# LED.net
KiCad netlist of a schematic drawn in Altium Designer
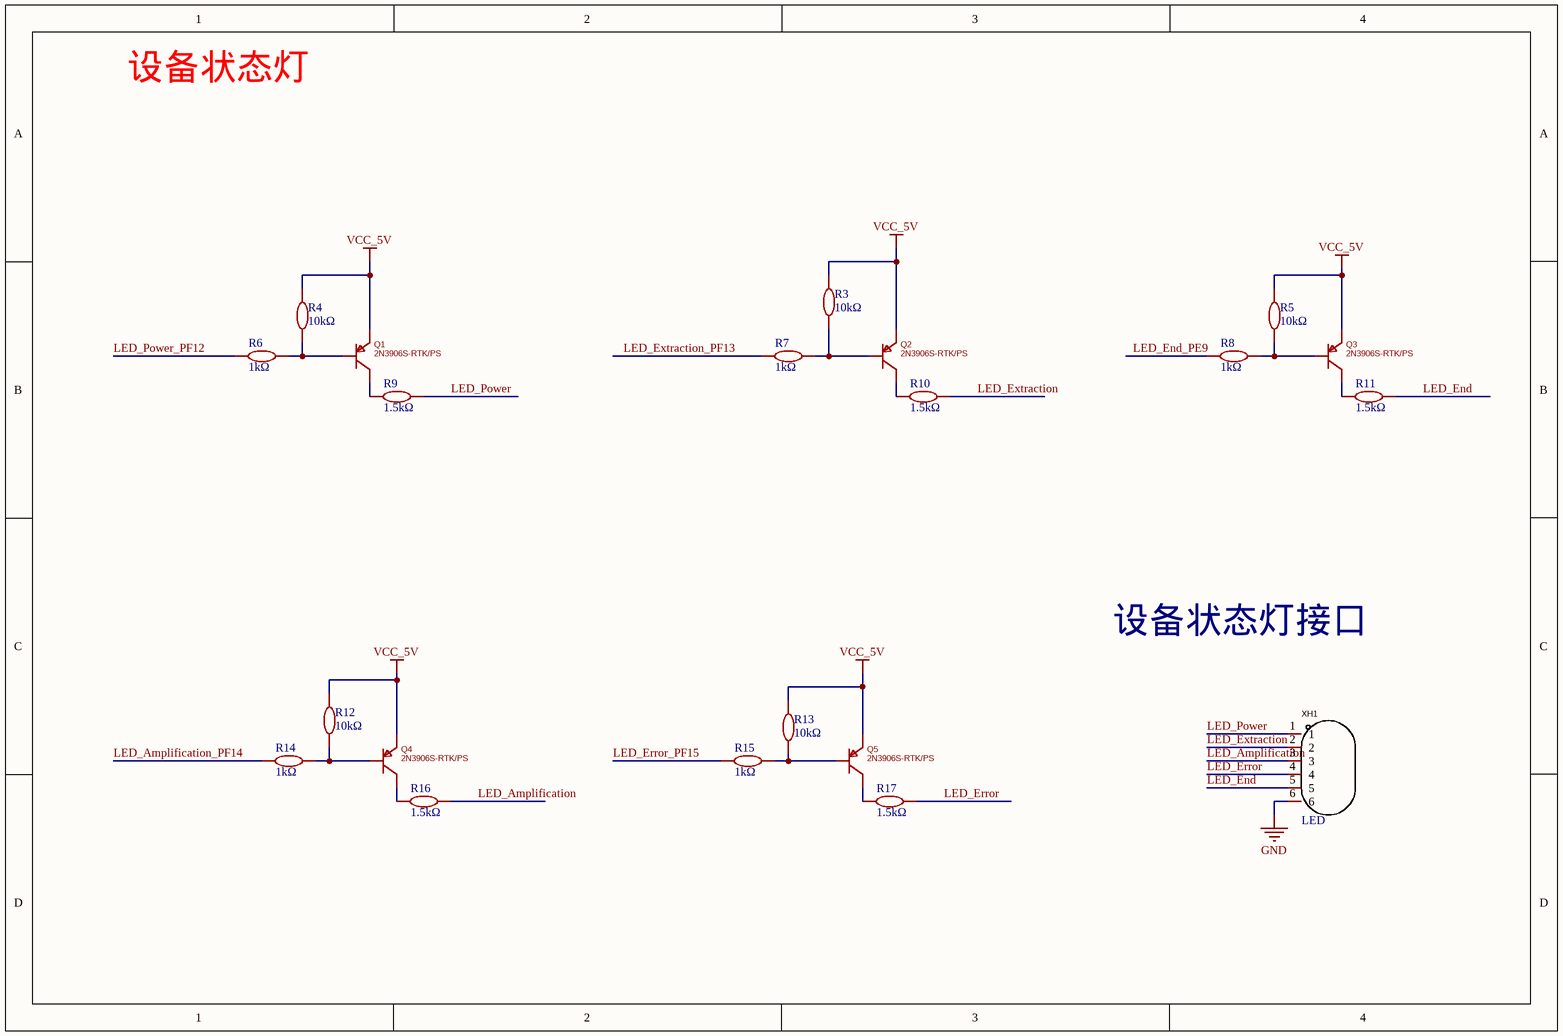
[diagram p0: LED.SchDoc]

(export (version "E")
  (design (tool "Eeschema 10.0.6"))
  (components
    (comp (ref "Q1")
      (value "2N3906S-RTK/PS")
      (footprint "SOT-23-3_L2.9-W1.3-P1.90-LS2.4-TR")
      (fields (field (name "MANUFACTURER") "KEC"))
      (libsource (lib "XG_DW_POCT_2K10LED_3") (part "2N3906S-RTK/PS"))
    )
    (comp (ref "Q2")
      (value "2N3906S-RTK/PS")
      (footprint "SOT-23-3_L2.9-W1.3-P1.90-LS2.4-TR")
      (fields (field (name "MANUFACTURER") "KEC"))
      (libsource (lib "XG_DW_POCT_2K10LED_3") (part "2N3906S-RTK/PS"))
    )
    (comp (ref "Q3")
      (value "2N3906S-RTK/PS")
      (footprint "SOT-23-3_L2.9-W1.3-P1.90-LS2.4-TR")
      (fields (field (name "MANUFACTURER") "KEC"))
      (libsource (lib "XG_DW_POCT_2K10LED_3") (part "2N3906S-RTK/PS"))
    )
    (comp (ref "Q4")
      (value "2N3906S-RTK/PS")
      (footprint "SOT-23-3_L2.9-W1.3-P1.90-LS2.4-TR")
      (fields (field (name "MANUFACTURER") "KEC"))
      (libsource (lib "XG_DW_POCT_2K10LED_3") (part "2N3906S-RTK/PS"))
    )
    (comp (ref "Q5")
      (value "2N3906S-RTK/PS")
      (footprint "SOT-23-3_L2.9-W1.3-P1.90-LS2.4-TR")
      (fields (field (name "MANUFACTURER") "KEC"))
      (libsource (lib "XG_DW_POCT_2K10LED_3") (part "2N3906S-RTK/PS"))
    )
    (comp (ref "R3")
      (value "10kΩ")
      (footprint "R0603")
      (description "电阻类型:厚膜电阻;阻值:10kΩ;精度:±1%;功率:100mW;最大工作电压:75V;温度系数:±100ppm/℃;")
      (libsource (lib "XG_DW_POCT_2K10LED_3") (part "10kΩ,R0603"))
    )
    (comp (ref "R4")
      (value "10kΩ")
      (footprint "R0603")
      (description "电阻类型:厚膜电阻;阻值:10kΩ;精度:±1%;功率:100mW;最大工作电压:75V;温度系数:±100ppm/℃;")
      (libsource (lib "XG_DW_POCT_2K10LED_3") (part "10kΩ,R0603"))
    )
    (comp (ref "R5")
      (value "10kΩ")
      (footprint "R0603")
      (description "电阻类型:厚膜电阻;阻值:10kΩ;精度:±1%;功率:100mW;最大工作电压:75V;温度系数:±100ppm/℃;")
      (libsource (lib "XG_DW_POCT_2K10LED_3") (part "10kΩ,R0603"))
    )
    (comp (ref "R6")
      (value "1kΩ")
      (footprint "R0603")
      (description "电阻类型:厚膜电阻;阻值:1kΩ;精度:±1%;功率:125mW;最大工作电压:150V;温度系数:±100ppm/℃;")
      (libsource (lib "XG_DW_POCT_2K10LED_3") (part "1kΩ,R0603"))
    )
    (comp (ref "R7")
      (value "1kΩ")
      (footprint "R0603")
      (description "电阻类型:厚膜电阻;阻值:1kΩ;精度:±1%;功率:125mW;最大工作电压:150V;温度系数:±100ppm/℃;")
      (libsource (lib "XG_DW_POCT_2K10LED_3") (part "1kΩ,R0603"))
    )
    (comp (ref "R8")
      (value "1kΩ")
      (footprint "R0603")
      (description "电阻类型:厚膜电阻;阻值:1kΩ;精度:±1%;功率:125mW;最大工作电压:150V;温度系数:±100ppm/℃;")
      (libsource (lib "XG_DW_POCT_2K10LED_3") (part "1kΩ,R0603"))
    )
    (comp (ref "R9")
      (value "1.5kΩ")
      (footprint "R0603")
      (description "电阻类型:厚膜电阻;阻值:1.5kΩ;精度:±1%;功率:100mW;最大工作电压:75V;温度系数:±100ppm/℃;")
      (libsource (lib "XG_DW_POCT_2K10LED_3") (part "1.5kΩ,R0603"))
    )
    (comp (ref "R10")
      (value "1.5kΩ")
      (footprint "R0603")
      (description "电阻类型:厚膜电阻;阻值:1.5kΩ;精度:±1%;功率:100mW;最大工作电压:75V;温度系数:±100ppm/℃;")
      (libsource (lib "XG_DW_POCT_2K10LED_3") (part "1.5kΩ,R0603"))
    )
    (comp (ref "R11")
      (value "1.5kΩ")
      (footprint "R0603")
      (description "电阻类型:厚膜电阻;阻值:1.5kΩ;精度:±1%;功率:100mW;最大工作电压:75V;温度系数:±100ppm/℃;")
      (libsource (lib "XG_DW_POCT_2K10LED_3") (part "1.5kΩ,R0603"))
    )
    (comp (ref "R12")
      (value "10kΩ")
      (footprint "R0603")
      (description "电阻类型:厚膜电阻;阻值:10kΩ;精度:±1%;功率:100mW;最大工作电压:75V;温度系数:±100ppm/℃;")
      (libsource (lib "XG_DW_POCT_2K10LED_3") (part "10kΩ,R0603"))
    )
    (comp (ref "R13")
      (value "10kΩ")
      (footprint "R0603")
      (description "电阻类型:厚膜电阻;阻值:10kΩ;精度:±1%;功率:100mW;最大工作电压:75V;温度系数:±100ppm/℃;")
      (libsource (lib "XG_DW_POCT_2K10LED_3") (part "10kΩ,R0603"))
    )
    (comp (ref "R14")
      (value "1kΩ")
      (footprint "R0603")
      (description "电阻类型:厚膜电阻;阻值:1kΩ;精度:±1%;功率:125mW;最大工作电压:150V;温度系数:±100ppm/℃;")
      (libsource (lib "XG_DW_POCT_2K10LED_3") (part "1kΩ,R0603"))
    )
    (comp (ref "R15")
      (value "1kΩ")
      (footprint "R0603")
      (description "电阻类型:厚膜电阻;阻值:1kΩ;精度:±1%;功率:125mW;最大工作电压:150V;温度系数:±100ppm/℃;")
      (libsource (lib "XG_DW_POCT_2K10LED_3") (part "1kΩ,R0603"))
    )
    (comp (ref "R16")
      (value "1.5kΩ")
      (footprint "R0603")
      (description "电阻类型:厚膜电阻;阻值:1.5kΩ;精度:±1%;功率:100mW;最大工作电压:75V;温度系数:±100ppm/℃;")
      (libsource (lib "XG_DW_POCT_2K10LED_3") (part "1.5kΩ,R0603"))
    )
    (comp (ref "R17")
      (value "1.5kΩ")
      (footprint "R0603")
      (description "电阻类型:厚膜电阻;阻值:1.5kΩ;精度:±1%;功率:100mW;最大工作电压:75V;温度系数:±100ppm/℃;")
      (libsource (lib "XG_DW_POCT_2K10LED_3") (part "1.5kΩ,R0603"))
    )
    (comp (ref "XH1")
      (value "LED")
      (footprint "CONN-TH_6P-P2.00_S6B-PH-K-S-LF-SN")
      (libsource (lib "XG_DW_POCT_2K10LED_3") (part "S6B-PH-K-S(LF)(SN)"))
    )
  )
  (nets
    (net (code "1") (name "/LED_Amplification") (class "Default")
      (node (ref "R16") (pin "1") (pinfunction "1_1") (pintype "passive"))
      (node (ref "XH1") (pin "3") (pinfunction "3_3") (pintype "passive"))
    )
    (net (code "2") (name "/LED_Amplification_PF14") (class "Default")
      (node (ref "R14") (pin "2") (pinfunction "2_2") (pintype "passive"))
    )
    (net (code "3") (name "/LED_End") (class "Default")
      (node (ref "R11") (pin "1") (pinfunction "1_1") (pintype "passive"))
      (node (ref "XH1") (pin "5") (pinfunction "5_5") (pintype "passive"))
    )
    (net (code "4") (name "/LED_End_PE9") (class "Default")
      (node (ref "R8") (pin "2") (pinfunction "2_2") (pintype "passive"))
    )
    (net (code "5") (name "/LED_Error") (class "Default")
      (node (ref "R17") (pin "1") (pinfunction "1_1") (pintype "passive"))
      (node (ref "XH1") (pin "4") (pinfunction "4_4") (pintype "passive"))
    )
    (net (code "6") (name "/LED_Error_PF15") (class "Default")
      (node (ref "R15") (pin "2") (pinfunction "2_2") (pintype "passive"))
    )
    (net (code "7") (name "/LED_Extraction") (class "Default")
      (node (ref "R10") (pin "1") (pinfunction "1_1") (pintype "passive"))
      (node (ref "XH1") (pin "2") (pinfunction "2_2") (pintype "passive"))
    )
    (net (code "8") (name "/LED_Extraction_PF13") (class "Default")
      (node (ref "R7") (pin "2") (pinfunction "2_2") (pintype "passive"))
    )
    (net (code "9") (name "/LED_Power") (class "Default")
      (node (ref "R9") (pin "2") (pinfunction "2_2") (pintype "passive"))
      (node (ref "XH1") (pin "1") (pinfunction "1_1") (pintype "passive"))
    )
    (net (code "10") (name "/LED_Power_PF12") (class "Default")
      (node (ref "R6") (pin "2") (pinfunction "2_2") (pintype "passive"))
    )
    (net (code "11") (name "GND") (class "Default")
      (node (ref "XH1") (pin "6") (pinfunction "6_6") (pintype "passive"))
    )
    (net (code "12") (name "Net-(Q1-B)") (class "Default")
      (node (ref "Q1") (pin "2") (pinfunction "B_2") (pintype "passive"))
      (node (ref "R4") (pin "1") (pinfunction "1_1") (pintype "passive"))
      (node (ref "R6") (pin "1") (pinfunction "1_1") (pintype "passive"))
    )
    (net (code "13") (name "Net-(Q1-C)") (class "Default")
      (node (ref "Q1") (pin "3") (pinfunction "C_3") (pintype "passive"))
      (node (ref "R9") (pin "1") (pinfunction "1_1") (pintype "passive"))
    )
    (net (code "14") (name "Net-(Q2-B)") (class "Default")
      (node (ref "Q2") (pin "2") (pinfunction "B_2") (pintype "passive"))
      (node (ref "R3") (pin "1") (pinfunction "1_1") (pintype "passive"))
      (node (ref "R7") (pin "1") (pinfunction "1_1") (pintype "passive"))
    )
    (net (code "15") (name "Net-(Q2-C)") (class "Default")
      (node (ref "Q2") (pin "3") (pinfunction "C_3") (pintype "passive"))
      (node (ref "R10") (pin "2") (pinfunction "2_2") (pintype "passive"))
    )
    (net (code "16") (name "Net-(Q3-B)") (class "Default")
      (node (ref "Q3") (pin "2") (pinfunction "B_2") (pintype "passive"))
      (node (ref "R5") (pin "1") (pinfunction "1_1") (pintype "passive"))
      (node (ref "R8") (pin "1") (pinfunction "1_1") (pintype "passive"))
    )
    (net (code "17") (name "Net-(Q3-C)") (class "Default")
      (node (ref "Q3") (pin "3") (pinfunction "C_3") (pintype "passive"))
      (node (ref "R11") (pin "2") (pinfunction "2_2") (pintype "passive"))
    )
    (net (code "18") (name "Net-(Q4-B)") (class "Default")
      (node (ref "Q4") (pin "2") (pinfunction "B_2") (pintype "passive"))
      (node (ref "R12") (pin "1") (pinfunction "1_1") (pintype "passive"))
      (node (ref "R14") (pin "1") (pinfunction "1_1") (pintype "passive"))
    )
    (net (code "19") (name "Net-(Q4-C)") (class "Default")
      (node (ref "Q4") (pin "3") (pinfunction "C_3") (pintype "passive"))
      (node (ref "R16") (pin "2") (pinfunction "2_2") (pintype "passive"))
    )
    (net (code "20") (name "Net-(Q5-B)") (class "Default")
      (node (ref "Q5") (pin "2") (pinfunction "B_2") (pintype "passive"))
      (node (ref "R13") (pin "1") (pinfunction "1_1") (pintype "passive"))
      (node (ref "R15") (pin "1") (pinfunction "1_1") (pintype "passive"))
    )
    (net (code "21") (name "Net-(Q5-C)") (class "Default")
      (node (ref "Q5") (pin "3") (pinfunction "C_3") (pintype "passive"))
      (node (ref "R17") (pin "2") (pinfunction "2_2") (pintype "passive"))
    )
    (net (code "22") (name "VCC_5V") (class "Default")
      (node (ref "Q1") (pin "1") (pinfunction "E_1") (pintype "passive"))
      (node (ref "Q2") (pin "1") (pinfunction "E_1") (pintype "passive"))
      (node (ref "Q3") (pin "1") (pinfunction "E_1") (pintype "passive"))
      (node (ref "Q4") (pin "1") (pinfunction "E_1") (pintype "passive"))
      (node (ref "Q5") (pin "1") (pinfunction "E_1") (pintype "passive"))
      (node (ref "R12") (pin "2") (pinfunction "2_2") (pintype "passive"))
      (node (ref "R13") (pin "2") (pinfunction "2_2") (pintype "passive"))
      (node (ref "R3") (pin "2") (pinfunction "2_2") (pintype "passive"))
      (node (ref "R4") (pin "2") (pinfunction "2_2") (pintype "passive"))
      (node (ref "R5") (pin "2") (pinfunction "2_2") (pintype "passive"))
    )
  )
)
